# untitled.net
KiCad netlist of a schematic drawn in EAGLE
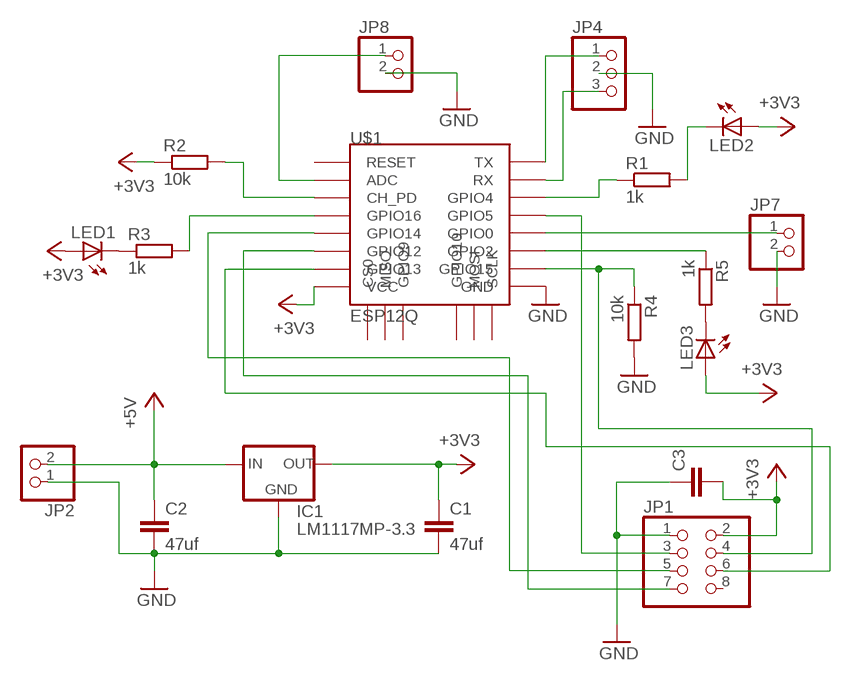
[diagram p0: schematic, sheet 1]

(export (version "E")
  (design (tool "Eeschema 10.0.6"))
  (components
    (comp (ref "C1")
      (value "47uf")
      (footprint "eagle-import:C1812K")
      (libsource (lib "eagle-import") (part "C-EUC1812K"))
    )
    (comp (ref "C2")
      (value "47uf")
      (footprint "eagle-import:C1812K")
      (libsource (lib "eagle-import") (part "C-EUC1812K"))
    )
    (comp (ref "C3")
      (value "C-EUC3216")
      (footprint "eagle-import:C3216")
      (libsource (lib "eagle-import") (part "C-EUC3216"))
    )
    (comp (ref "IC1")
      (value "LM1117MP-3.3")
      (footprint "eagle-import:SOT223")
      (fields (field (name "MF") "Texas Instruments"))
      (libsource (lib "eagle-import") (part "LM1117?-MP3.3"))
    )
    (comp (ref "JP1")
      (value "PINHD-2X4")
      (footprint "eagle-import:2X04")
      (libsource (lib "eagle-import") (part "PINHD-2X4"))
    )
    (comp (ref "JP2")
      (value "PINHD-1X2")
      (footprint "eagle-import:1X02")
      (libsource (lib "eagle-import") (part "PINHD-1X2"))
    )
    (comp (ref "JP4")
      (value "PINHD-1X3")
      (footprint "eagle-import:1X03")
      (libsource (lib "eagle-import") (part "PINHD-1X3"))
    )
    (comp (ref "JP7")
      (value "PINHD-1X2")
      (footprint "eagle-import:1X02")
      (libsource (lib "eagle-import") (part "PINHD-1X2"))
    )
    (comp (ref "JP8")
      (value "PINHD-1X2")
      (footprint "eagle-import:1X02")
      (libsource (lib "eagle-import") (part "PINHD-1X2"))
    )
    (comp (ref "LED1")
      (value "LEDSFH482")
      (footprint "eagle-import:SFH482")
      (libsource (lib "eagle-import") (part "LEDSFH482"))
    )
    (comp (ref "LED2")
      (value "LEDSFH482")
      (footprint "eagle-import:SFH482")
      (libsource (lib "eagle-import") (part "LEDSFH482"))
    )
    (comp (ref "LED3")
      (value "LEDSFH482")
      (footprint "eagle-import:SFH482")
      (libsource (lib "eagle-import") (part "LEDSFH482"))
    )
    (comp (ref "R1")
      (value "1k")
      (footprint "eagle-import:R0805")
      (libsource (lib "eagle-import") (part "R-EU_R0805"))
    )
    (comp (ref "R2")
      (value "10k")
      (footprint "eagle-import:0207_12")
      (libsource (lib "eagle-import") (part "R-EU_0207/12"))
    )
    (comp (ref "R3")
      (value "1k")
      (footprint "eagle-import:R0805")
      (libsource (lib "eagle-import") (part "R-EU_R0805"))
    )
    (comp (ref "R4")
      (value "10k")
      (footprint "eagle-import:M0805")
      (libsource (lib "eagle-import") (part "R-EU_M0805"))
    )
    (comp (ref "R5")
      (value "1k")
      (footprint "eagle-import:R0805")
      (libsource (lib "eagle-import") (part "R-EU_R0805"))
    )
    (comp (ref "U$1")
      (value "ESP12Q")
      (footprint "eagle-import:ESP12Q")
      (libsource (lib "eagle-import") (part "ESP12Q"))
    )
  )
  (nets
    (net (code "1") (name "+3V3") (class "Default")
      (node (ref "C1") (pin "1") (pinfunction "1_1") (pintype "passive"))
      (node (ref "C3") (pin "2") (pinfunction "2_2") (pintype "passive"))
      (node (ref "IC1") (pin "2") (pinfunction "OUT_2") (pintype "passive"))
      (node (ref "IC1") (pin "4") (pinfunction "OUT_4") (pintype "passive"))
      (node (ref "JP1") (pin "2") (pinfunction "2_2") (pintype "passive"))
      (node (ref "LED1") (pin "A") (pinfunction "A_A") (pintype "passive"))
      (node (ref "LED2") (pin "A") (pinfunction "A_A") (pintype "passive"))
      (node (ref "LED3") (pin "A") (pinfunction "A_A") (pintype "passive"))
      (node (ref "R2") (pin "1") (pinfunction "1_1") (pintype "passive"))
      (node (ref "U$1") (pin "VCC") (pinfunction "VCC_VCC") (pintype "bidirectional"))
    )
    (net (code "2") (name "+5V") (class "Default")
      (node (ref "C2") (pin "1") (pinfunction "1_1") (pintype "passive"))
      (node (ref "IC1") (pin "3") (pinfunction "IN_3") (pintype "input"))
      (node (ref "JP2") (pin "2") (pinfunction "2_2") (pintype "passive"))
    )
    (net (code "3") (name "GND") (class "Default")
      (node (ref "C1") (pin "2") (pinfunction "2_2") (pintype "passive"))
      (node (ref "C2") (pin "2") (pinfunction "2_2") (pintype "passive"))
      (node (ref "C3") (pin "1") (pinfunction "1_1") (pintype "passive"))
      (node (ref "IC1") (pin "1") (pinfunction "GND_1") (pintype "input"))
      (node (ref "JP1") (pin "1") (pinfunction "1_1") (pintype "passive"))
      (node (ref "JP2") (pin "1") (pinfunction "1_1") (pintype "passive"))
      (node (ref "JP4") (pin "2") (pinfunction "2_2") (pintype "passive"))
      (node (ref "JP7") (pin "2") (pinfunction "2_2") (pintype "passive"))
      (node (ref "JP8") (pin "2") (pinfunction "2_2") (pintype "passive"))
      (node (ref "R4") (pin "2") (pinfunction "2_2") (pintype "passive"))
      (node (ref "U$1") (pin "GND") (pinfunction "GND_GND") (pintype "bidirectional"))
    )
    (net (code "4") (name "Net-(JP1-Pad3)") (class "Default")
      (node (ref "JP1") (pin "3") (pinfunction "3_3") (pintype "passive"))
      (node (ref "U$1") (pin "GPIO5") (pinfunction "GPIO5_GPIO5") (pintype "bidirectional"))
    )
    (net (code "5") (name "Net-(JP1-Pad4)") (class "Default")
      (node (ref "JP1") (pin "4") (pinfunction "4_4") (pintype "passive"))
      (node (ref "R4") (pin "1") (pinfunction "1_1") (pintype "passive"))
      (node (ref "U$1") (pin "GPIO15") (pinfunction "GPIO15_GPIO15") (pintype "bidirectional"))
    )
    (net (code "6") (name "Net-(JP1-Pad5)") (class "Default")
      (node (ref "JP1") (pin "5") (pinfunction "5_5") (pintype "passive"))
      (node (ref "U$1") (pin "GPIO14") (pinfunction "GPIO14_GPIO14") (pintype "bidirectional"))
    )
    (net (code "7") (name "Net-(JP1-Pad6)") (class "Default")
      (node (ref "JP1") (pin "6") (pinfunction "6_6") (pintype "passive"))
      (node (ref "U$1") (pin "GPIO13") (pinfunction "GPIO13_GPIO13") (pintype "bidirectional"))
    )
    (net (code "8") (name "Net-(JP1-Pad7)") (class "Default")
      (node (ref "JP1") (pin "7") (pinfunction "7_7") (pintype "passive"))
      (node (ref "U$1") (pin "GPIO12") (pinfunction "GPIO12_GPIO12") (pintype "bidirectional"))
    )
    (net (code "9") (name "Net-(JP4-Pad1)") (class "Default")
      (node (ref "JP4") (pin "1") (pinfunction "1_1") (pintype "passive"))
      (node (ref "U$1") (pin "TX") (pinfunction "TX_TX") (pintype "bidirectional"))
    )
    (net (code "10") (name "Net-(JP4-Pad3)") (class "Default")
      (node (ref "JP4") (pin "3") (pinfunction "3_3") (pintype "passive"))
      (node (ref "U$1") (pin "RX") (pinfunction "RX_RX") (pintype "bidirectional"))
    )
    (net (code "11") (name "Net-(JP7-Pad1)") (class "Default")
      (node (ref "JP7") (pin "1") (pinfunction "1_1") (pintype "passive"))
      (node (ref "U$1") (pin "GPIO0") (pinfunction "GPIO0_GPIO0") (pintype "bidirectional"))
    )
    (net (code "12") (name "Net-(JP8-Pad1)") (class "Default")
      (node (ref "JP8") (pin "1") (pinfunction "1_1") (pintype "passive"))
      (node (ref "U$1") (pin "ADC") (pinfunction "ADC_ADC") (pintype "bidirectional"))
    )
    (net (code "13") (name "Net-(LED1-C)") (class "Default")
      (node (ref "LED1") (pin "K") (pinfunction "C_K") (pintype "passive"))
      (node (ref "R3") (pin "1") (pinfunction "1_1") (pintype "passive"))
    )
    (net (code "14") (name "Net-(LED2-C)") (class "Default")
      (node (ref "LED2") (pin "K") (pinfunction "C_K") (pintype "passive"))
      (node (ref "R1") (pin "2") (pinfunction "2_2") (pintype "passive"))
    )
    (net (code "15") (name "Net-(LED3-C)") (class "Default")
      (node (ref "LED3") (pin "K") (pinfunction "C_K") (pintype "passive"))
      (node (ref "R5") (pin "2") (pinfunction "2_2") (pintype "passive"))
    )
    (net (code "16") (name "Net-(R1-Pad1)") (class "Default")
      (node (ref "R1") (pin "1") (pinfunction "1_1") (pintype "passive"))
      (node (ref "U$1") (pin "GPIO4") (pinfunction "GPIO4_GPIO4") (pintype "bidirectional"))
    )
    (net (code "17") (name "Net-(R2-Pad2)") (class "Default")
      (node (ref "R2") (pin "2") (pinfunction "2_2") (pintype "passive"))
      (node (ref "U$1") (pin "CH_PD") (pinfunction "CH_PD_CH_PD") (pintype "bidirectional"))
    )
    (net (code "18") (name "Net-(R3-Pad2)") (class "Default")
      (node (ref "R3") (pin "2") (pinfunction "2_2") (pintype "passive"))
      (node (ref "U$1") (pin "GPIO16") (pinfunction "GPIO16_GPIO16") (pintype "bidirectional"))
    )
    (net (code "19") (name "Net-(R5-Pad1)") (class "Default")
      (node (ref "R5") (pin "1") (pinfunction "1_1") (pintype "passive"))
      (node (ref "U$1") (pin "GPIO2") (pinfunction "GPIO2_GPIO2") (pintype "bidirectional"))
    )
    (net (code "20") (name "unconnected-(JP1-Pad8)") (class "Default")
      (node (ref "JP1") (pin "8") (pinfunction "8_8") (pintype "passive"))
    )
    (net (code "21") (name "unconnected-(U$1-PadCS0)") (class "Default")
      (node (ref "U$1") (pin "CS0") (pinfunction "CS0_CS0") (pintype "bidirectional"))
    )
    (net (code "22") (name "unconnected-(U$1-PadGPIO9)") (class "Default")
      (node (ref "U$1") (pin "GPIO9") (pinfunction "GPIO9_GPIO9") (pintype "bidirectional"))
    )
    (net (code "23") (name "unconnected-(U$1-PadGPIO10)") (class "Default")
      (node (ref "U$1") (pin "GPIO10") (pinfunction "GPIO10_GPIO10") (pintype "bidirectional"))
    )
    (net (code "24") (name "unconnected-(U$1-PadMISO)") (class "Default")
      (node (ref "U$1") (pin "MISO") (pinfunction "MISO_MISO") (pintype "bidirectional"))
    )
    (net (code "25") (name "unconnected-(U$1-PadMOSI)") (class "Default")
      (node (ref "U$1") (pin "MOSI") (pinfunction "MOSI_MOSI") (pintype "bidirectional"))
    )
    (net (code "26") (name "unconnected-(U$1-PadRESET)") (class "Default")
      (node (ref "U$1") (pin "RESET") (pinfunction "RESET_RESET") (pintype "bidirectional"))
    )
    (net (code "27") (name "unconnected-(U$1-PadSCLK)") (class "Default")
      (node (ref "U$1") (pin "SCLK") (pinfunction "SCLK_SCLK") (pintype "bidirectional"))
    )
  )
)
